# ac-timer.net
KiCad netlist of a schematic drawn in EAGLE
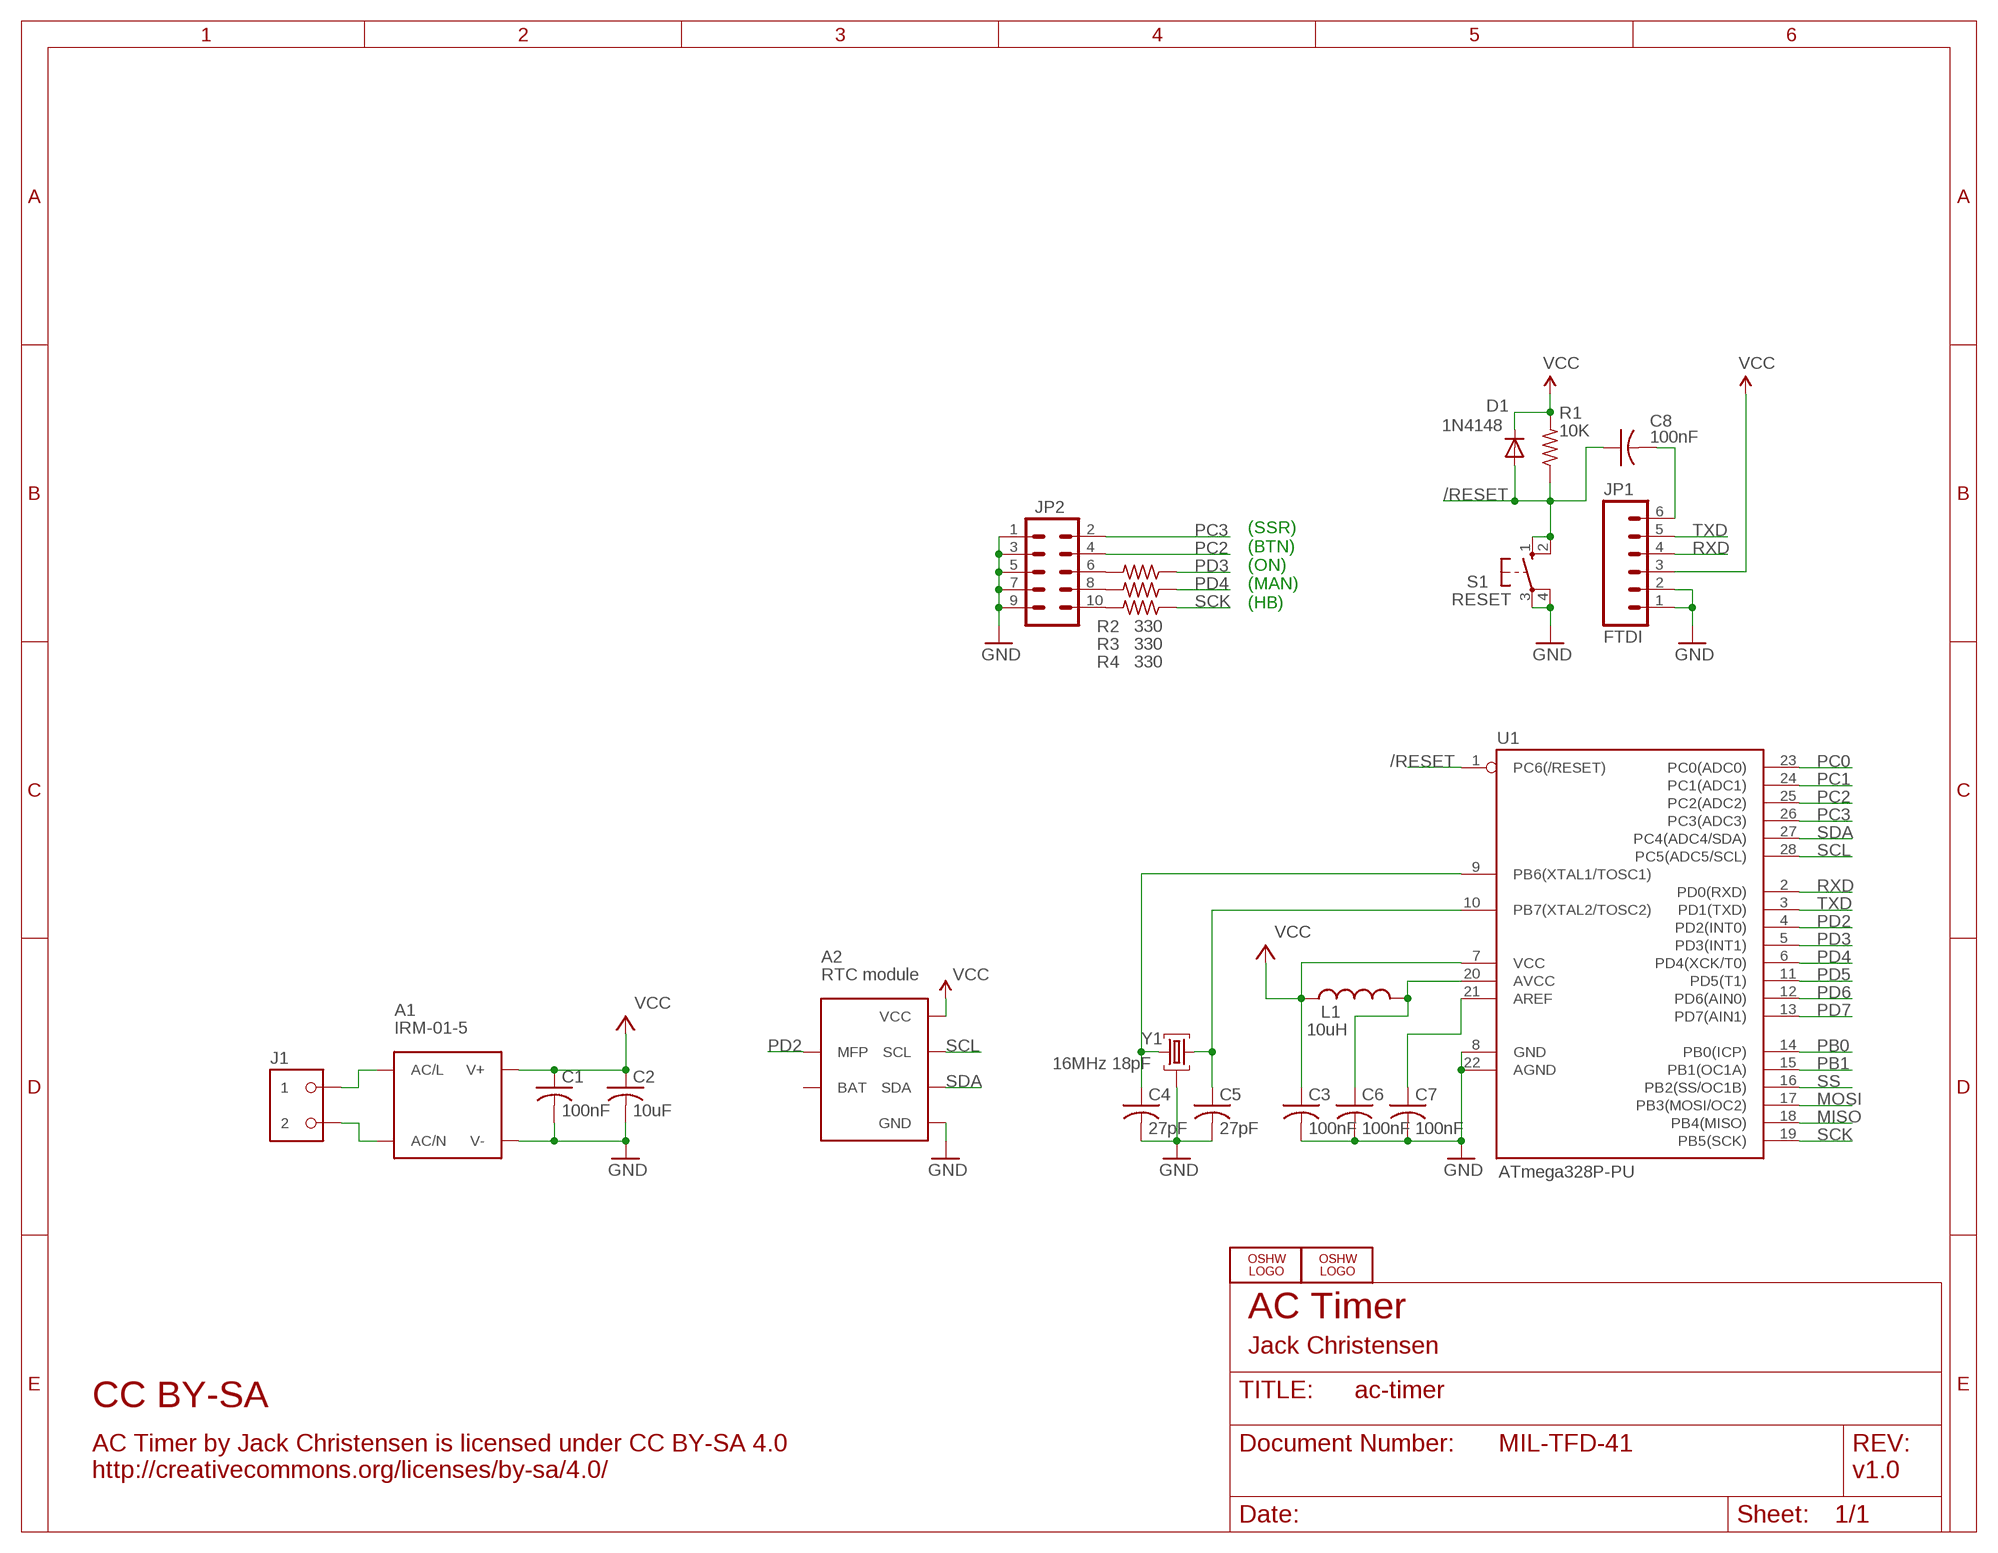
[diagram p0: schematic, sheet 1]

(export (version "E")
  (design (tool "Eeschema 10.0.6"))
  (components
    (comp (ref "A1")
      (value "IRM-01-5")
      (footprint "eagle-import:IRM-01")
      (libsource (lib "eagle-import") (part "IRM-01"))
    )
    (comp (ref "A2")
      (value "RTC module")
      (footprint "eagle-import:RTC79412")
      (libsource (lib "eagle-import") (part "RTC79412"))
    )
    (comp (ref "C1")
      (value "100nF")
      (footprint "eagle-import:M0805")
      (libsource (lib "eagle-import") (part "C-USM0805"))
    )
    (comp (ref "C2")
      (value "10uF")
      (footprint "eagle-import:M0805")
      (libsource (lib "eagle-import") (part "C-USM0805"))
    )
    (comp (ref "C3")
      (value "100nF")
      (footprint "eagle-import:M0805")
      (libsource (lib "eagle-import") (part "C-USM0805"))
    )
    (comp (ref "C4")
      (value "27pF")
      (footprint "eagle-import:M0805")
      (libsource (lib "eagle-import") (part "C-USM0805"))
    )
    (comp (ref "C5")
      (value "27pF")
      (footprint "eagle-import:M0805")
      (libsource (lib "eagle-import") (part "C-USM0805"))
    )
    (comp (ref "C6")
      (value "100nF")
      (footprint "eagle-import:M0805")
      (libsource (lib "eagle-import") (part "C-USM0805"))
    )
    (comp (ref "C7")
      (value "100nF")
      (footprint "eagle-import:M0805")
      (libsource (lib "eagle-import") (part "C-USM0805"))
    )
    (comp (ref "C8")
      (value "100nF")
      (footprint "eagle-import:M0805")
      (libsource (lib "eagle-import") (part "C-USM0805"))
    )
    (comp (ref "D1")
      (value "1N4148")
      (footprint "eagle-import:SOD-323F")
      (libsource (lib "eagle-import") (part "DIODESOD-323F"))
    )
    (comp (ref "J1")
      (value "OST-TB-20.20IN")
      (footprint "eagle-import:OST-TB-2-0.20")
      (libsource (lib "eagle-import") (part "OST-TB-20.20IN"))
    )
    (comp (ref "JP1")
      (value "FTDI")
      (footprint "eagle-import:1X06_LOCK")
      (libsource (lib "eagle-import") (part "M06LOCK"))
    )
    (comp (ref "JP2")
      (value "M05X2PTH")
      (footprint "eagle-import:AVR_ICSP")
      (libsource (lib "eagle-import") (part "M05X2PTH"))
    )
    (comp (ref "L1")
      (value "10uH")
      (footprint "eagle-import:M0805")
      (libsource (lib "eagle-import") (part "INDUCTORM0805"))
    )
    (comp (ref "LOGO1")
      (value "OSHW_LOGO_8MILX0100-NT")
      (footprint "eagle-import:OSHW_8X100_NOTEXT")
      (libsource (lib "eagle-import") (part "OSHW_LOGO_8MILX0100-NT"))
    )
    (comp (ref "LOGO2")
      (value "OSHW_LOGO_8MILX0100-NT")
      (footprint "eagle-import:OSHW_8X100_NOTEXT")
      (libsource (lib "eagle-import") (part "OSHW_LOGO_8MILX0100-NT"))
    )
    (comp (ref "R1")
      (value "10K")
      (footprint "eagle-import:M0805")
      (libsource (lib "eagle-import") (part "R-US_M0805"))
    )
    (comp (ref "R2")
      (value "330")
      (footprint "eagle-import:M0805")
      (libsource (lib "eagle-import") (part "R-US_M0805"))
    )
    (comp (ref "R3")
      (value "330")
      (footprint "eagle-import:M0805")
      (libsource (lib "eagle-import") (part "R-US_M0805"))
    )
    (comp (ref "R4")
      (value "330")
      (footprint "eagle-import:M0805")
      (libsource (lib "eagle-import") (part "R-US_M0805"))
    )
    (comp (ref "S1")
      (value "RESET")
      (footprint "eagle-import:B3F-10XXOCT")
      (libsource (lib "eagle-import") (part "10-XXOCT"))
    )
    (comp (ref "U1")
      (value "ATmega328P-PU")
      (footprint "eagle-import:DIL28-3")
      (libsource (lib "eagle-import") (part "AVR-MEGA8-PPTH"))
    )
    (comp (ref "Y1")
      (value "16MHz 18pF")
      (footprint "eagle-import:RESONATOR")
      (libsource (lib "eagle-import") (part "RESONATOR"))
    )
  )
  (nets
    (net (code "1") (name "/MISO") (class "Default")
      (node (ref "U1") (pin "18") (pinfunction "PB4(MISO)_18") (pintype "bidirectional"))
    )
    (net (code "2") (name "/MOSI") (class "Default")
      (node (ref "U1") (pin "17") (pinfunction "PB3(MOSI/OC2)_17") (pintype "bidirectional"))
    )
    (net (code "3") (name "/PB0") (class "Default")
      (node (ref "U1") (pin "14") (pinfunction "PB0(ICP)_14") (pintype "bidirectional"))
    )
    (net (code "4") (name "/PB1") (class "Default")
      (node (ref "U1") (pin "15") (pinfunction "PB1(OC1A)_15") (pintype "bidirectional"))
    )
    (net (code "5") (name "/PC0") (class "Default")
      (node (ref "U1") (pin "23") (pinfunction "PC0(ADC0)_23") (pintype "bidirectional"))
    )
    (net (code "6") (name "/PC1") (class "Default")
      (node (ref "U1") (pin "24") (pinfunction "PC1(ADC1)_24") (pintype "bidirectional"))
    )
    (net (code "7") (name "/PC2") (class "Default")
      (node (ref "JP2") (pin "4") (pinfunction "4_4") (pintype "passive"))
      (node (ref "U1") (pin "25") (pinfunction "PC2(ADC2)_25") (pintype "bidirectional"))
    )
    (net (code "8") (name "/PC3") (class "Default")
      (node (ref "JP2") (pin "2") (pinfunction "2_2") (pintype "passive"))
      (node (ref "U1") (pin "26") (pinfunction "PC3(ADC3)_26") (pintype "bidirectional"))
    )
    (net (code "9") (name "/PD2") (class "Default")
      (node (ref "A2") (pin "3") (pinfunction "MFP_3") (pintype "passive"))
      (node (ref "U1") (pin "4") (pinfunction "PD2(INT0)_4") (pintype "bidirectional"))
    )
    (net (code "10") (name "/PD3") (class "Default")
      (node (ref "R2") (pin "1") (pinfunction "1_1") (pintype "passive"))
      (node (ref "U1") (pin "5") (pinfunction "PD3(INT1)_5") (pintype "bidirectional"))
    )
    (net (code "11") (name "/PD4") (class "Default")
      (node (ref "R3") (pin "1") (pinfunction "1_1") (pintype "passive"))
      (node (ref "U1") (pin "6") (pinfunction "PD4(XCK/T0)_6") (pintype "bidirectional"))
    )
    (net (code "12") (name "/PD5") (class "Default")
      (node (ref "U1") (pin "11") (pinfunction "PD5(T1)_11") (pintype "bidirectional"))
    )
    (net (code "13") (name "/PD6") (class "Default")
      (node (ref "U1") (pin "12") (pinfunction "PD6(AIN0)_12") (pintype "bidirectional"))
    )
    (net (code "14") (name "/PD7") (class "Default")
      (node (ref "U1") (pin "13") (pinfunction "PD7(AIN1)_13") (pintype "bidirectional"))
    )
    (net (code "15") (name "/RXD") (class "Default")
      (node (ref "JP1") (pin "4") (pinfunction "4_4") (pintype "passive"))
      (node (ref "U1") (pin "2") (pinfunction "PD0(RXD)_2") (pintype "bidirectional"))
    )
    (net (code "16") (name "/SCK") (class "Default")
      (node (ref "R4") (pin "1") (pinfunction "1_1") (pintype "passive"))
      (node (ref "U1") (pin "19") (pinfunction "PB5(SCK)_19") (pintype "bidirectional"))
    )
    (net (code "17") (name "/SCL") (class "Default")
      (node (ref "A2") (pin "6") (pinfunction "SCL_6") (pintype "passive"))
      (node (ref "U1") (pin "28") (pinfunction "PC5(ADC5/SCL)_28") (pintype "bidirectional"))
    )
    (net (code "18") (name "/SDA") (class "Default")
      (node (ref "A2") (pin "5") (pinfunction "SDA_5") (pintype "passive"))
      (node (ref "U1") (pin "27") (pinfunction "PC4(ADC4/SDA)_27") (pintype "bidirectional"))
    )
    (net (code "19") (name "/SS") (class "Default")
      (node (ref "U1") (pin "16") (pinfunction "PB2(SS/OC1B)_16") (pintype "bidirectional"))
    )
    (net (code "20") (name "/TXD") (class "Default")
      (node (ref "JP1") (pin "5") (pinfunction "5_5") (pintype "passive"))
      (node (ref "U1") (pin "3") (pinfunction "PD1(TXD)_3") (pintype "bidirectional"))
    )
    (net (code "21") (name "/{slash}RESET") (class "Default")
      (node (ref "C8") (pin "1") (pinfunction "1_1") (pintype "passive"))
      (node (ref "D1") (pin "A") (pinfunction "A_A") (pintype "passive"))
      (node (ref "R1") (pin "1") (pinfunction "1_1") (pintype "passive"))
      (node (ref "S1") (pin "1") (pinfunction "S_1") (pintype "passive"))
      (node (ref "S1") (pin "2") (pinfunction "S1_2") (pintype "passive"))
      (node (ref "U1") (pin "1") (pinfunction "PC6(/RESET)_1") (pintype "bidirectional"))
    )
    (net (code "22") (name "GND") (class "Default")
      (node (ref "A1") (pin "V-") (pinfunction "V-_V-") (pintype "bidirectional"))
      (node (ref "A2") (pin "8") (pinfunction "GND_8") (pintype "passive"))
      (node (ref "C1") (pin "2") (pinfunction "2_2") (pintype "passive"))
      (node (ref "C2") (pin "2") (pinfunction "2_2") (pintype "passive"))
      (node (ref "C3") (pin "2") (pinfunction "2_2") (pintype "passive"))
      (node (ref "C4") (pin "2") (pinfunction "2_2") (pintype "passive"))
      (node (ref "C5") (pin "2") (pinfunction "2_2") (pintype "passive"))
      (node (ref "C6") (pin "2") (pinfunction "2_2") (pintype "passive"))
      (node (ref "C7") (pin "2") (pinfunction "2_2") (pintype "passive"))
      (node (ref "JP1") (pin "1") (pinfunction "1_1") (pintype "passive"))
      (node (ref "JP1") (pin "2") (pinfunction "2_2") (pintype "passive"))
      (node (ref "JP2") (pin "1") (pinfunction "1_1") (pintype "passive"))
      (node (ref "JP2") (pin "3") (pinfunction "3_3") (pintype "passive"))
      (node (ref "JP2") (pin "5") (pinfunction "5_5") (pintype "passive"))
      (node (ref "JP2") (pin "7") (pinfunction "7_7") (pintype "passive"))
      (node (ref "JP2") (pin "9") (pinfunction "9_9") (pintype "passive"))
      (node (ref "S1") (pin "3") (pinfunction "P_3") (pintype "passive"))
      (node (ref "S1") (pin "4") (pinfunction "P1_4") (pintype "passive"))
      (node (ref "U1") (pin "22") (pinfunction "AGND_22") (pintype "bidirectional"))
      (node (ref "U1") (pin "8") (pinfunction "GND_8") (pintype "bidirectional"))
      (node (ref "Y1") (pin "2") (pinfunction "2_2") (pintype "passive"))
    )
    (net (code "23") (name "Net-(C8-Pad2)") (class "Default")
      (node (ref "C8") (pin "2") (pinfunction "2_2") (pintype "passive"))
      (node (ref "JP1") (pin "6") (pinfunction "6_6") (pintype "passive"))
    )
    (net (code "24") (name "Net-(J1-1)") (class "Default")
      (node (ref "A1") (pin "AC/L") (pinfunction "AC/L_AC/L") (pintype "bidirectional"))
      (node (ref "J1") (pin "P$1") (pinfunction "1_P$1") (pintype "passive"))
    )
    (net (code "25") (name "Net-(J1-2)") (class "Default")
      (node (ref "A1") (pin "AC/N") (pinfunction "AC/N_AC/N") (pintype "bidirectional"))
      (node (ref "J1") (pin "P$2") (pinfunction "2_P$2") (pintype "passive"))
    )
    (net (code "26") (name "Net-(JP2-Pad6)") (class "Default")
      (node (ref "JP2") (pin "6") (pinfunction "6_6") (pintype "passive"))
      (node (ref "R2") (pin "2") (pinfunction "2_2") (pintype "passive"))
    )
    (net (code "27") (name "Net-(JP2-Pad8)") (class "Default")
      (node (ref "JP2") (pin "8") (pinfunction "8_8") (pintype "passive"))
      (node (ref "R3") (pin "2") (pinfunction "2_2") (pintype "passive"))
    )
    (net (code "28") (name "Net-(JP2-Pad10)") (class "Default")
      (node (ref "JP2") (pin "10") (pinfunction "10_10") (pintype "passive"))
      (node (ref "R4") (pin "2") (pinfunction "2_2") (pintype "passive"))
    )
    (net (code "29") (name "Net-(U1-AREF)") (class "Default")
      (node (ref "C7") (pin "1") (pinfunction "1_1") (pintype "passive"))
      (node (ref "U1") (pin "21") (pinfunction "AREF_21") (pintype "bidirectional"))
    )
    (net (code "30") (name "Net-(U1-AVCC)") (class "Default")
      (node (ref "C6") (pin "1") (pinfunction "1_1") (pintype "passive"))
      (node (ref "L1") (pin "2") (pinfunction "2_2") (pintype "passive"))
      (node (ref "U1") (pin "20") (pinfunction "AVCC_20") (pintype "bidirectional"))
    )
    (net (code "31") (name "Net-(U1-PB6(XTAL1{slash}TOSC1))") (class "Default")
      (node (ref "C4") (pin "1") (pinfunction "1_1") (pintype "passive"))
      (node (ref "U1") (pin "9") (pinfunction "PB6(XTAL1/TOSC1)_9") (pintype "bidirectional"))
      (node (ref "Y1") (pin "1") (pinfunction "1_1") (pintype "passive"))
    )
    (net (code "32") (name "Net-(U1-PB7(XTAL2{slash}TOSC2))") (class "Default")
      (node (ref "C5") (pin "1") (pinfunction "1_1") (pintype "passive"))
      (node (ref "U1") (pin "10") (pinfunction "PB7(XTAL2/TOSC2)_10") (pintype "bidirectional"))
      (node (ref "Y1") (pin "3") (pinfunction "3_3") (pintype "passive"))
    )
    (net (code "33") (name "VCC") (class "Default")
      (node (ref "A1") (pin "V+") (pinfunction "V+_V+") (pintype "bidirectional"))
      (node (ref "A2") (pin "7") (pinfunction "VCC_7") (pintype "passive"))
      (node (ref "C1") (pin "1") (pinfunction "1_1") (pintype "passive"))
      (node (ref "C2") (pin "1") (pinfunction "1_1") (pintype "passive"))
      (node (ref "C3") (pin "1") (pinfunction "1_1") (pintype "passive"))
      (node (ref "D1") (pin "K") (pinfunction "K_K") (pintype "passive"))
      (node (ref "JP1") (pin "3") (pinfunction "3_3") (pintype "passive"))
      (node (ref "L1") (pin "1") (pinfunction "1_1") (pintype "passive"))
      (node (ref "R1") (pin "2") (pinfunction "2_2") (pintype "passive"))
      (node (ref "U1") (pin "7") (pinfunction "VCC_7") (pintype "bidirectional"))
    )
    (net (code "34") (name "unconnected-(A2-BAT-Pad1)") (class "Default")
      (node (ref "A2") (pin "1") (pinfunction "BAT_1") (pintype "passive"))
    )
  )
)
